# SCH_PCB1_2026-10-08.net
KiCad netlist of a schematic drawn in EasyEDA
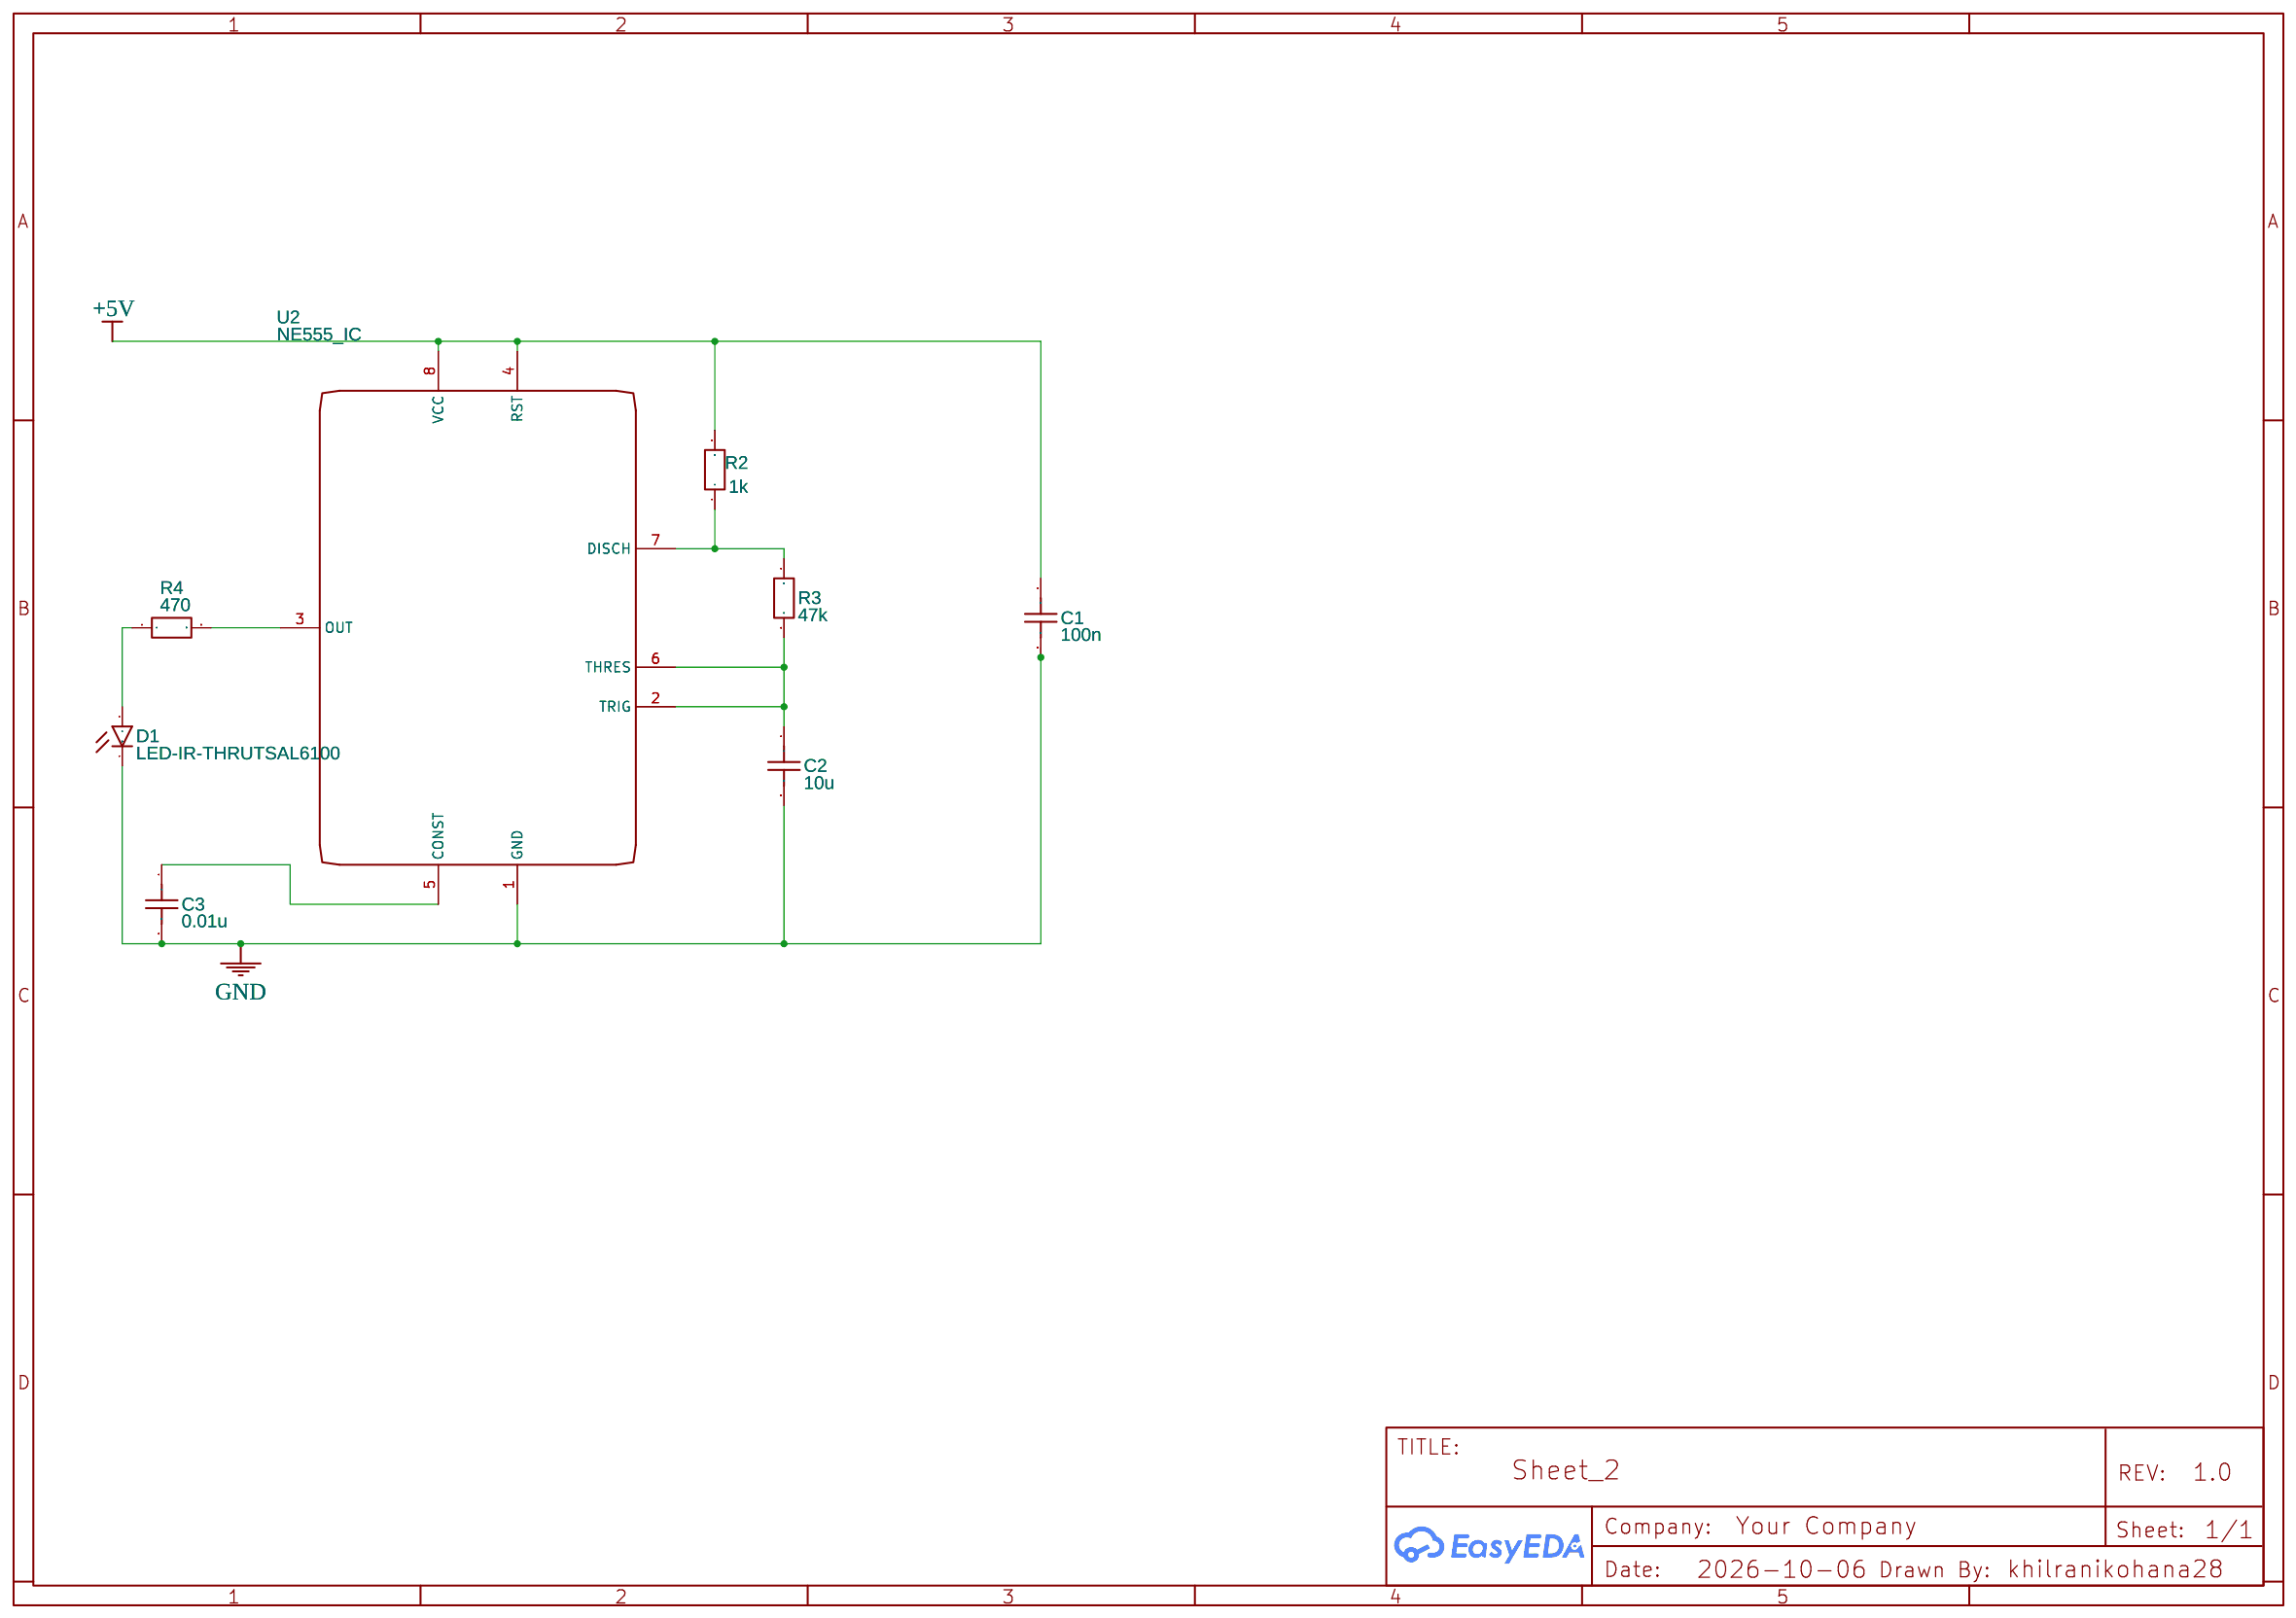
[diagram p0: Sheet_2]
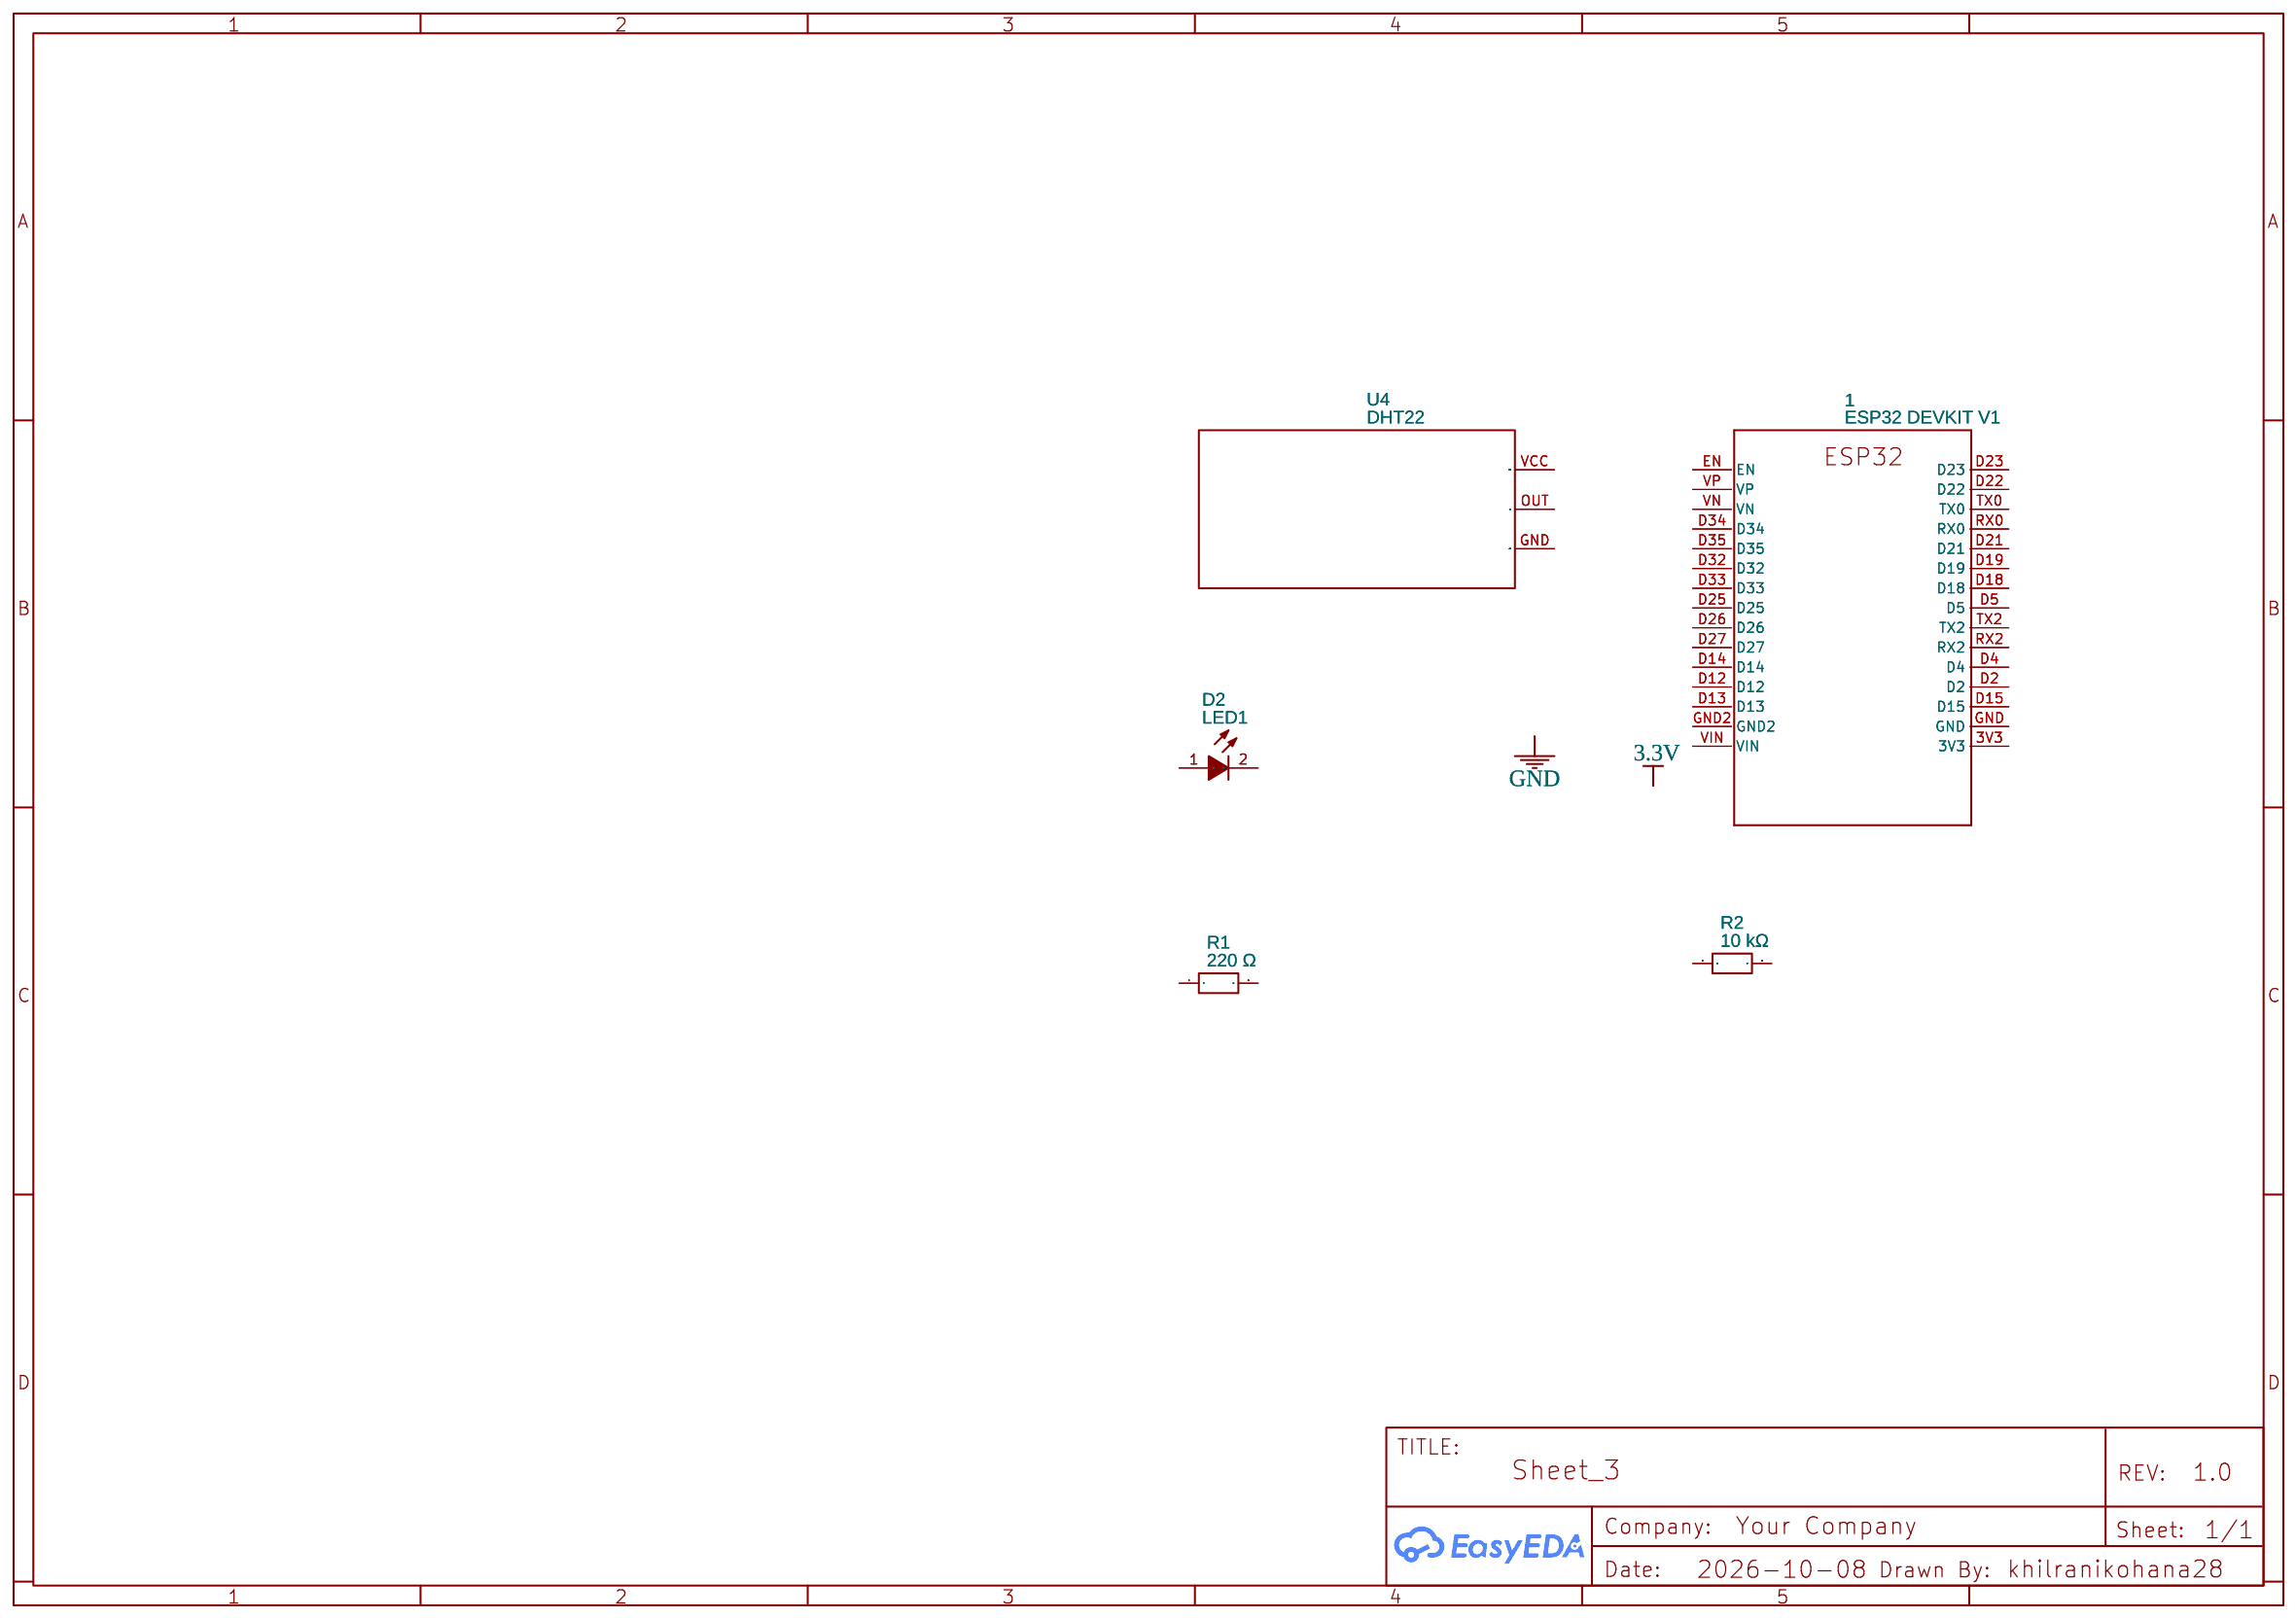
[diagram p1: Sheet_3]

(export (version "E")
  (design (tool "Eeschema 10.0.6"))
  (components
    (comp (ref "C1") (value "100n") (libsource (lib "") (part "C_0603_US")))
    (comp (ref "C2") (value "10u") (libsource (lib "") (part "C_0603_US")))
    (comp (ref "C3") (value "0.01u") (libsource (lib "") (part "C_0603_US")))
    (comp (ref "D1") (value "LED-IR-THRUTSAL6100") (libsource (lib "") (part "LED-IR-THRUTSAL6100")))
    (comp (ref "R2") (value "1k") (libsource (lib "") (part "R_0603_EU")))
    (comp (ref "R3") (value "47k") (libsource (lib "") (part "R_0603_EU_2")))
    (comp (ref "R4") (value "470") (libsource (lib "") (part "R_0603_EU_1")))
    (comp (ref "U2")
      (value "NE555_IC")
      (fields (field (name "Manufacturer Part") "NE555") (field (name "Manufacturer") "Diodes Incorporation"))
      (libsource (lib "") (part "NE555_IC"))
    )
    (comp (ref "1") (value "ESP32 DEVKIT V1") (libsource (lib "") (part "ESP32-DEVKIT-V1-30PIN")))
    (comp (ref "D2")
      (value "LED1")
      (fields (field (name "Manufacturer Part") "5600") (field (name "Manufacturer") "VccLite"))
      (libsource (lib "") (part "LED"))
    )
    (comp (ref "R1") (value "220 Ω") (libsource (lib "") (part "R_0603_EU")))
    (comp (ref "R2") (value "1k") (libsource (lib "") (part "R_0603_EU")))
    (comp (ref "U4") (value "DHT22") (libsource (lib "") (part "DHT22")))
  )
  (nets
    (net (code "1") (name "+5V") (class "Default")
      (node (ref "C1") (pin "1") (pinfunction "1_1") (pintype "unspecified"))
      (node (ref "R2") (pin "2") (pinfunction "2_2") (pintype "unspecified"))
      (node (ref "U2") (pin "4") (pinfunction "RST_4") (pintype "input"))
      (node (ref "U2") (pin "8") (pinfunction "VCC_8") (pintype "passive"))
    )
    (net (code "3") (name "GND") (class "Default")
      (node (ref "C1") (pin "2") (pinfunction "2_2") (pintype "unspecified"))
      (node (ref "C2") (pin "2") (pinfunction "2_2") (pintype "unspecified"))
      (node (ref "C3") (pin "2") (pinfunction "2_2") (pintype "unspecified"))
      (node (ref "D1") (pin "K") (pinfunction "C_K") (pintype "unspecified"))
      (node (ref "U2") (pin "1") (pinfunction "GND_1") (pintype "passive"))
    )
    (net (code "4") (name "Net-(D1-PadA)") (class "Default")
      (node (ref "D1") (pin "A") (pinfunction "A_A") (pintype "unspecified"))
      (node (ref "R4") (pin "1") (pinfunction "1_1") (pintype "unspecified"))
    )
    (net (code "5") (name "Net-(U2-CONST)") (class "Default")
      (node (ref "C3") (pin "1") (pinfunction "1_1") (pintype "unspecified"))
      (node (ref "U2") (pin "5") (pinfunction "CONST_5") (pintype "input"))
    )
    (net (code "6") (name "Net-(U2-DISCH)") (class "Default")
      (node (ref "R2") (pin "1") (pinfunction "1_1") (pintype "unspecified"))
      (node (ref "R3") (pin "1") (pinfunction "1_1") (pintype "unspecified"))
      (node (ref "U2") (pin "7") (pinfunction "DISCH_7") (pintype "output"))
    )
    (net (code "7") (name "Net-(U2-OUT)") (class "Default")
      (node (ref "R4") (pin "2") (pinfunction "2_2") (pintype "unspecified"))
      (node (ref "U2") (pin "3") (pinfunction "OUT_3") (pintype "output"))
    )
    (net (code "8") (name "Net-(U2-THRES)") (class "Default")
      (node (ref "C2") (pin "1") (pinfunction "1_1") (pintype "unspecified"))
      (node (ref "R3") (pin "2") (pinfunction "2_2") (pintype "unspecified"))
      (node (ref "U2") (pin "2") (pinfunction "TRIG_2") (pintype "input"))
      (node (ref "U2") (pin "6") (pinfunction "THRES_6") (pintype "input"))
    )
    (net (code "9") (name "unconnected-(1-Pad3V3)") (class "Default")
      (node (ref "1") (pin "3V3") (pinfunction "3V3_3V3") (pintype "unspecified"))
    )
    (net (code "10") (name "unconnected-(1-PadD2)") (class "Default")
      (node (ref "1") (pin "D2") (pinfunction "D2_D2") (pintype "unspecified"))
    )
    (net (code "11") (name "unconnected-(1-PadD4)") (class "Default")
      (node (ref "1") (pin "D4") (pinfunction "D4_D4") (pintype "unspecified"))
    )
    (net (code "12") (name "unconnected-(1-PadD5)") (class "Default")
      (node (ref "1") (pin "D5") (pinfunction "D5_D5") (pintype "unspecified"))
    )
    (net (code "13") (name "unconnected-(1-PadD12)") (class "Default")
      (node (ref "1") (pin "D12") (pinfunction "D12_D12") (pintype "unspecified"))
    )
    (net (code "14") (name "unconnected-(1-PadD13)") (class "Default")
      (node (ref "1") (pin "D13") (pinfunction "D13_D13") (pintype "unspecified"))
    )
    (net (code "15") (name "unconnected-(1-PadD14)") (class "Default")
      (node (ref "1") (pin "D14") (pinfunction "D14_D14") (pintype "unspecified"))
    )
    (net (code "16") (name "unconnected-(1-PadD15)") (class "Default")
      (node (ref "1") (pin "D15") (pinfunction "D15_D15") (pintype "unspecified"))
    )
    (net (code "17") (name "unconnected-(1-PadD18)") (class "Default")
      (node (ref "1") (pin "D18") (pinfunction "D18_D18") (pintype "unspecified"))
    )
    (net (code "18") (name "unconnected-(1-PadD19)") (class "Default")
      (node (ref "1") (pin "D19") (pinfunction "D19_D19") (pintype "unspecified"))
    )
    (net (code "19") (name "unconnected-(1-PadD21)") (class "Default")
      (node (ref "1") (pin "D21") (pinfunction "D21_D21") (pintype "unspecified"))
    )
    (net (code "20") (name "unconnected-(1-PadD22)") (class "Default")
      (node (ref "1") (pin "D22") (pinfunction "D22_D22") (pintype "unspecified"))
    )
    (net (code "21") (name "unconnected-(1-PadD23)") (class "Default")
      (node (ref "1") (pin "D23") (pinfunction "D23_D23") (pintype "unspecified"))
    )
    (net (code "22") (name "unconnected-(1-PadD25)") (class "Default")
      (node (ref "1") (pin "D25") (pinfunction "D25_D25") (pintype "unspecified"))
    )
    (net (code "23") (name "unconnected-(1-PadD26)") (class "Default")
      (node (ref "1") (pin "D26") (pinfunction "D26_D26") (pintype "unspecified"))
    )
    (net (code "24") (name "unconnected-(1-PadD27)") (class "Default")
      (node (ref "1") (pin "D27") (pinfunction "D27_D27") (pintype "unspecified"))
    )
    (net (code "25") (name "unconnected-(1-PadD32)") (class "Default")
      (node (ref "1") (pin "D32") (pinfunction "D32_D32") (pintype "unspecified"))
    )
    (net (code "26") (name "unconnected-(1-PadD33)") (class "Default")
      (node (ref "1") (pin "D33") (pinfunction "D33_D33") (pintype "unspecified"))
    )
    (net (code "27") (name "unconnected-(1-PadD34)") (class "Default")
      (node (ref "1") (pin "D34") (pinfunction "D34_D34") (pintype "unspecified"))
    )
    (net (code "28") (name "unconnected-(1-PadD35)") (class "Default")
      (node (ref "1") (pin "D35") (pinfunction "D35_D35") (pintype "unspecified"))
    )
    (net (code "29") (name "unconnected-(1-PadEN)") (class "Default")
      (node (ref "1") (pin "EN") (pinfunction "EN_EN") (pintype "unspecified"))
    )
    (net (code "30") (name "unconnected-(1-PadGND)") (class "Default")
      (node (ref "1") (pin "GND") (pinfunction "GND_GND") (pintype "unspecified"))
    )
    (net (code "31") (name "unconnected-(1-PadGND2)") (class "Default")
      (node (ref "1") (pin "GND2") (pinfunction "GND2_GND2") (pintype "unspecified"))
    )
    (net (code "32") (name "unconnected-(1-PadRX0)") (class "Default")
      (node (ref "1") (pin "RX0") (pinfunction "RX0_RX0") (pintype "unspecified"))
    )
    (net (code "33") (name "unconnected-(1-PadRX2)") (class "Default")
      (node (ref "1") (pin "RX2") (pinfunction "RX2_RX2") (pintype "unspecified"))
    )
    (net (code "34") (name "unconnected-(1-PadTX0)") (class "Default")
      (node (ref "1") (pin "TX0") (pinfunction "TX0_TX0") (pintype "unspecified"))
    )
    (net (code "35") (name "unconnected-(1-PadTX2)") (class "Default")
      (node (ref "1") (pin "TX2") (pinfunction "TX2_TX2") (pintype "unspecified"))
    )
    (net (code "36") (name "unconnected-(1-PadVIN)") (class "Default")
      (node (ref "1") (pin "VIN") (pinfunction "VIN_VIN") (pintype "unspecified"))
    )
    (net (code "37") (name "unconnected-(1-PadVN)") (class "Default")
      (node (ref "1") (pin "VN") (pinfunction "VN_VN") (pintype "unspecified"))
    )
    (net (code "38") (name "unconnected-(1-PadVP)") (class "Default")
      (node (ref "1") (pin "VP") (pinfunction "VP_VP") (pintype "unspecified"))
    )
    (net (code "39") (name "unconnected-(D2-A-Pad1)") (class "Default")
      (node (ref "D2") (pin "1") (pinfunction "A_1") (pintype "unspecified"))
    )
    (net (code "40") (name "unconnected-(D2-K-Pad2)") (class "Default")
      (node (ref "D2") (pin "2") (pinfunction "K_2") (pintype "unspecified"))
    )
    (net (code "41") (name "unconnected-(R1-Pad1)") (class "Default")
      (node (ref "R1") (pin "1") (pinfunction "1_1") (pintype "unspecified"))
    )
    (net (code "42") (name "unconnected-(R1-Pad2)") (class "Default")
      (node (ref "R1") (pin "2") (pinfunction "2_2") (pintype "unspecified"))
    )
    (net (code "43") (name "unconnected-(R2-Pad1)") (class "Default")
      (node (ref "R2") (pin "1") (pinfunction "1_1") (pintype "unspecified"))
    )
    (net (code "44") (name "unconnected-(R2-Pad2)") (class "Default")
      (node (ref "R2") (pin "2") (pinfunction "2_2") (pintype "unspecified"))
    )
    (net (code "45") (name "unconnected-(U4-5v-PadOUT)") (class "Default")
      (node (ref "U4") (pin "OUT") (pinfunction "5v_OUT") (pintype "unspecified"))
    )
    (net (code "46") (name "unconnected-(U4-data-PadVCC)") (class "Default")
      (node (ref "U4") (pin "VCC") (pinfunction "data_VCC") (pintype "unspecified"))
    )
    (net (code "47") (name "unconnected-(U4-gnd-PadGND)") (class "Default")
      (node (ref "U4") (pin "GND") (pinfunction "gnd_GND") (pintype "unspecified"))
    )
  )
)
